# Sheet1.net
KiCad netlist of a schematic drawn in Altium Designer
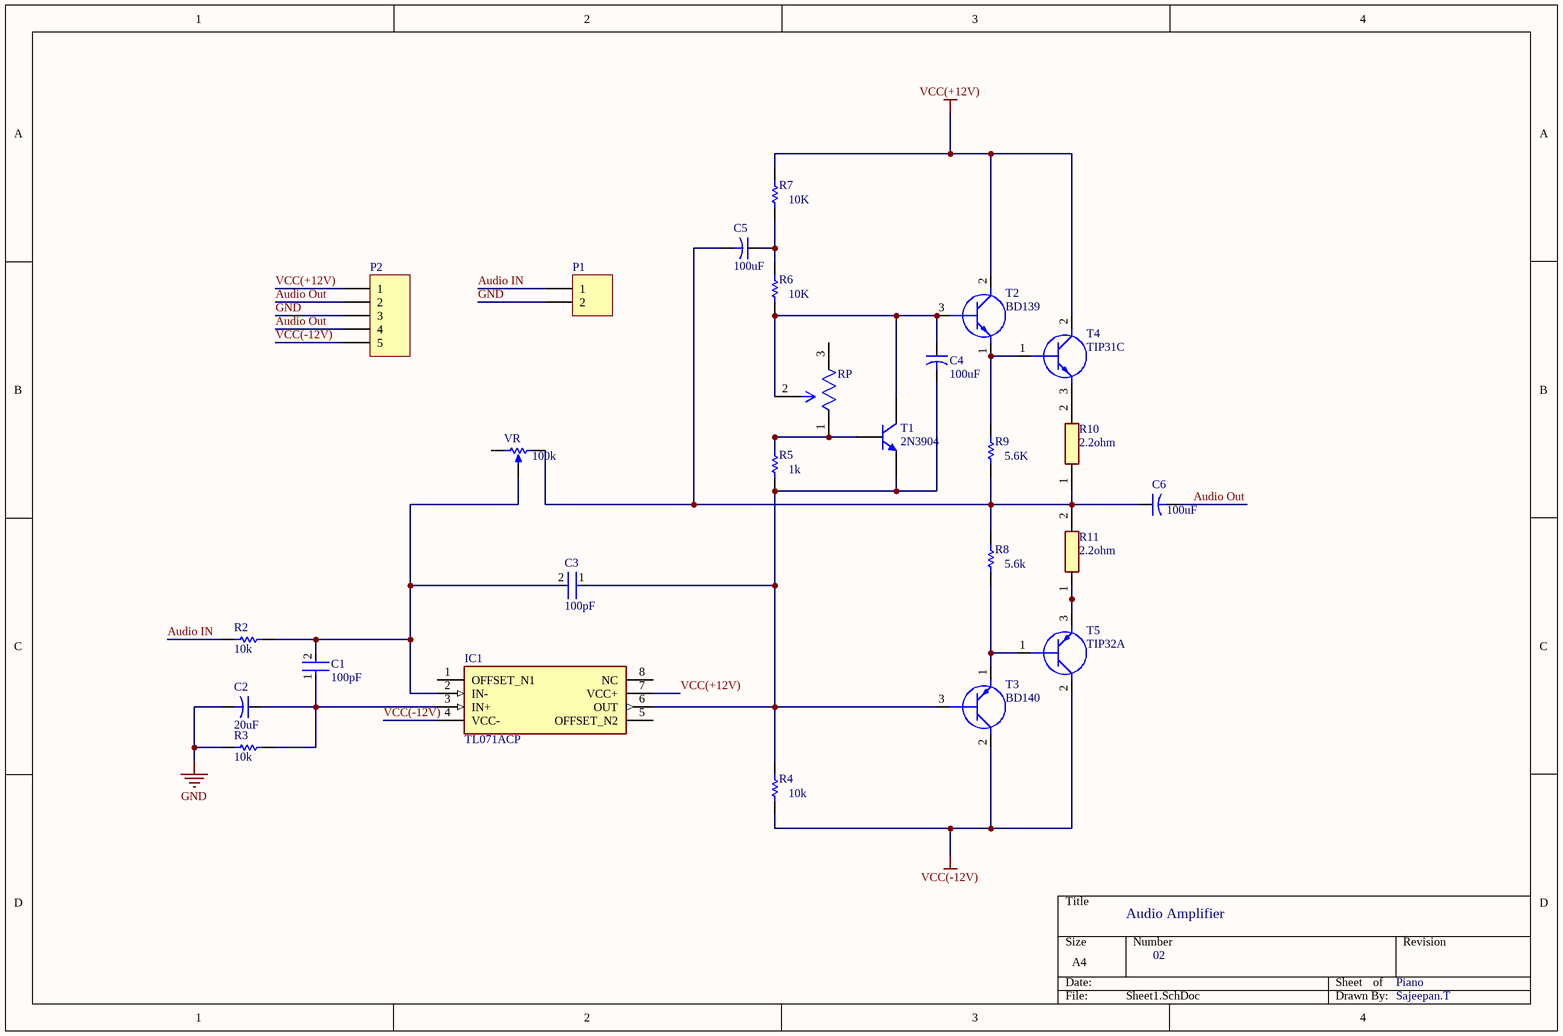
[diagram p0: Sheet1.SchDoc]

(export (version "E")
  (design (tool "Eeschema 10.0.6"))
  (components
    (comp (ref "C1")
      (value "100pF")
      (footprint "FP-RHS0DG-MFG")
      (description "CAP CER 100PF 100V CCG THRUHOLE")
      (fields (field (name "TOLERANCE") "5%") (field (name "MANUFACTURER") "Murata"))
      (libsource (lib "Altium Content Vault") (part "b4654b650e69147ec39a6b967a45e02"))
    )
    (comp (ref "C2")
      (value "20uF")
      (footprint "CAPR5-4X5")
      (description "Capacitor")
      (fields (field (name "Comment") "Cap2") (field (name "PUBLISHER") "Altium Limited"))
      (libsource (lib "Miscellaneous Devices") (part "Cap2"))
    )
    (comp (ref "C3")
      (value "100pF")
      (footprint "FP-RHS0DG-MFG")
      (description "CAP CER 100PF 100V CCG THRUHOLE")
      (fields (field (name "TOLERANCE") "5%") (field (name "MANUFACTURER") "Murata"))
      (libsource (lib "Altium Content Vault") (part "b4654b650e69147ec39a6b967a45e02"))
    )
    (comp (ref "C4")
      (value "100uF")
      (footprint "CAPR5-4X5")
      (description "Capacitor")
      (fields (field (name "Comment") "Cap2") (field (name "PUBLISHER") "Altium Limited"))
      (libsource (lib "Miscellaneous Devices") (part "Cap2"))
    )
    (comp (ref "C5")
      (value "100uF")
      (footprint "CAPR5-4X5")
      (description "Capacitor")
      (fields (field (name "Comment") "Cap2") (field (name "PUBLISHER") "Altium Limited"))
      (libsource (lib "Miscellaneous Devices") (part "Cap2"))
    )
    (comp (ref "C6")
      (value "100uF")
      (footprint "CAPR5-4X5")
      (description "Capacitor")
      (fields (field (name "Comment") "Cap2") (field (name "PUBLISHER") "Altium Limited"))
      (libsource (lib "Miscellaneous Devices") (part "Cap2"))
    )
    (comp (ref "IC1")
      (value "TL071ACP")
      (footprint "SamacSys:DIP794W53P254L959H508Q8N")
      (description "Integrated Circuit")
      (fields (field (name "MOUSER PART NUMBER") "595-TL071ACP"))
      (libsource (lib "*") (part "TL071ACP"))
    )
    (comp (ref "P1")
      (value "Header 2")
      (footprint "HDR1X2")
      (description "Header, 2-Pin")
      (fields (field (name "PUBLISHER") "Altium Limited"))
      (libsource (lib "Miscellaneous Connectors") (part "Header 2"))
    )
    (comp (ref "P2")
      (value "Header 5")
      (footprint "HDR1X5")
      (description "Header, 5-Pin")
      (fields (field (name "PUBLISHER") "Altium Limited"))
      (libsource (lib "Miscellaneous Connectors") (part "Header 5"))
    )
    (comp (ref "R2")
      (value "10k")
      (footprint "AXIAL-0.3")
      (description "Resistor")
      (fields (field (name "Comment") "Res1") (field (name "PUBLISHER") "Altium Limited"))
      (libsource (lib "Miscellaneous Devices") (part "Res1"))
    )
    (comp (ref "R3")
      (value "10k")
      (footprint "AXIAL-0.3")
      (description "Resistor")
      (fields (field (name "Comment") "Res1") (field (name "PUBLISHER") "Altium Limited"))
      (libsource (lib "Miscellaneous Devices") (part "Res1"))
    )
    (comp (ref "R4")
      (value "10k")
      (footprint "AXIAL-0.3")
      (description "Resistor")
      (fields (field (name "Comment") "Res1") (field (name "PUBLISHER") "Altium Limited"))
      (libsource (lib "Miscellaneous Devices") (part "Res1"))
    )
    (comp (ref "R5")
      (value "1k")
      (footprint "AXIAL-0.3")
      (description "Resistor")
      (fields (field (name "Comment") "Res1") (field (name "PUBLISHER") "Altium Limited"))
      (libsource (lib "Miscellaneous Devices") (part "Res1"))
    )
    (comp (ref "R6")
      (value "10K")
      (footprint "AXIAL-0.3")
      (description "Resistor")
      (fields (field (name "Comment") "Res1") (field (name "PUBLISHER") "Altium Limited"))
      (libsource (lib "Miscellaneous Devices") (part "Res1"))
    )
    (comp (ref "R7")
      (value "10K")
      (footprint "AXIAL-0.3")
      (description "Resistor")
      (fields (field (name "Comment") "Res1") (field (name "PUBLISHER") "Altium Limited"))
      (libsource (lib "Miscellaneous Devices") (part "Res1"))
    )
    (comp (ref "R8")
      (value "5.6k")
      (footprint "AXIAL-0.3")
      (description "Resistor")
      (fields (field (name "Comment") "Res1") (field (name "PUBLISHER") "Altium Limited"))
      (libsource (lib "Miscellaneous Devices") (part "Res1"))
    )
    (comp (ref "R9")
      (value "5.6K")
      (footprint "AXIAL-0.3")
      (description "Resistor")
      (fields (field (name "Comment") "Res1") (field (name "PUBLISHER") "Altium Limited"))
      (libsource (lib "Miscellaneous Devices") (part "Res1"))
    )
    (comp (ref "R10")
      (value "2.2ohm")
      (footprint "SamacSys:RESAD1130W50L370D190")
      (description "Resistor")
      (fields (field (name "MANUFACTURER_PART_NUMBER") "MFF04FF6800A5"))
      (libsource (lib "*") (part "MFF04FF6800A5"))
    )
    (comp (ref "R11")
      (value "2.2ohm")
      (footprint "SamacSys:RESAD1130W50L370D190")
      (description "Resistor")
      (fields (field (name "MANUFACTURER_PART_NUMBER") "MFF04FF6800A5"))
      (libsource (lib "*") (part "MFF04FF6800A5"))
    )
    (comp (ref "RP")
      (value "3386F-1-303LF")
      (footprint "FP-3386F-MFG")
      (description "TRIMMER 30K OHM 0.5W PC PIN TOP")
      (fields
        (field (name "TOLERANCE") "10%")
        (field (name "OCTOPART") "https://octopart.com/3386f-1-303lf-bourns-1032328")
      )
      (libsource (lib "Altium Content Vault") (part "f696fc322aeaec4039820165aa0401c"))
    )
    (comp (ref "T1")
      (value "2N3904")
      (footprint "TO-92A")
      (description "NPN General Purpose Amplifier")
      (fields (field (name "PUBLISHER") "Altium Limited"))
      (libsource (lib "Miscellaneous Devices") (part "2N3904"))
    )
    (comp (ref "T2")
      (value "BD139")
      (footprint "SamacSys:TO229P300X760X1364-3P")
      (description "Transistor BJT NPN")
      (fields (field (name "MOUSER PART NUMBER") "863-BD139"))
      (libsource (lib "*") (part "BD139"))
    )
    (comp (ref "T3")
      (value "BD140")
      (footprint "SamacSys:TO229P345X800X1460-3P")
      (description "Transistor BJT PNP")
      (fields
        (field (name "MANUFACTURER_PART_NUMBER") "BD14010STU")
        (field (name "MOUSER PART NUMBER") "512-BD14010STU")
      )
      (libsource (lib "*") (part "BD14010STU"))
    )
    (comp (ref "T4")
      (value "TIP31C")
      (footprint "SamacSys:TO254P470X1016X2019-3P")
      (description "Transistor BJT NPN")
      (libsource (lib "*") (part "TIP31C"))
    )
    (comp (ref "T5")
      (value "TIP32A")
      (footprint "SamacSys:TO254P470X1016X2019-3P")
      (description "Transistor BJT PNP")
      (fields (field (name "MOUSER PART NUMBER") "512-TIP32A"))
      (libsource (lib "*") (part "TIP32A"))
    )
    (comp (ref "VR")
      (value "100k")
      (footprint "BOUR-3852A-282-103AL-3_V")
      (description "Diameter Panel Control, 10 KOhm, +/- 10%, 2 W, -1 to 125 degC, 3-Pin THD, RoHS, Bulk")
      (fields (field (name "TOLERANCE") "±10%") (field (name "MANUFACTURER") "Bourns"))
      (libsource (lib "Altium Content Vault") (part "RES-POT-3"))
    )
  )
  (nets
    (net (code "1") (name "/Audio IN") (class "Default")
      (node (ref "P1") (pin "1") (pinfunction "1_1") (pintype "passive"))
      (node (ref "R2") (pin "2") (pinfunction "2_2") (pintype "passive"))
    )
    (net (code "2") (name "/Audio Out") (class "Default")
      (node (ref "C6") (pin "2") (pinfunction "2_2") (pintype "passive"))
      (node (ref "P2") (pin "2") (pinfunction "2_2") (pintype "passive"))
      (node (ref "P2") (pin "4") (pinfunction "4_4") (pintype "passive"))
    )
    (net (code "3") (name "GND") (class "Default")
      (node (ref "C2") (pin "2") (pinfunction "2_2") (pintype "passive"))
      (node (ref "P1") (pin "2") (pinfunction "2_2") (pintype "passive"))
      (node (ref "P2") (pin "3") (pinfunction "3_3") (pintype "passive"))
      (node (ref "R3") (pin "2") (pinfunction "2_2") (pintype "passive"))
    )
    (net (code "4") (name "Net-(C5-Pad1)") (class "Default")
      (node (ref "C5") (pin "1") (pinfunction "1_1") (pintype "passive"))
      (node (ref "R6") (pin "2") (pinfunction "2_2") (pintype "passive"))
      (node (ref "R7") (pin "1") (pinfunction "1_1") (pintype "passive"))
    )
    (net (code "5") (name "Net-(IC1-IN+)") (class "Default")
      (node (ref "C1") (pin "1") (pinfunction "1_1") (pintype "passive"))
      (node (ref "C2") (pin "1") (pinfunction "1_1") (pintype "passive"))
      (node (ref "IC1") (pin "3") (pinfunction "IN+_3") (pintype "input"))
      (node (ref "R3") (pin "1") (pinfunction "1_1") (pintype "passive"))
    )
    (net (code "6") (name "Net-(IC1-IN-)") (class "Default")
      (node (ref "C1") (pin "2") (pinfunction "2_2") (pintype "passive"))
      (node (ref "C3") (pin "2") (pinfunction "2_2") (pintype "passive"))
      (node (ref "IC1") (pin "2") (pinfunction "IN-_2") (pintype "input"))
      (node (ref "R2") (pin "1") (pinfunction "1_1") (pintype "passive"))
      (node (ref "VR") (pin "2") (pinfunction "S_2") (pintype "passive"))
    )
    (net (code "7") (name "Net-(IC1-OUT)") (class "Default")
      (node (ref "C3") (pin "1") (pinfunction "1_1") (pintype "passive"))
      (node (ref "C4") (pin "2") (pinfunction "2_2") (pintype "passive"))
      (node (ref "IC1") (pin "6") (pinfunction "OUT_6") (pintype "output"))
      (node (ref "R4") (pin "2") (pinfunction "2_2") (pintype "passive"))
      (node (ref "R5") (pin "1") (pinfunction "1_1") (pintype "passive"))
      (node (ref "T1") (pin "1") (pinfunction "E_1") (pintype "passive"))
      (node (ref "T3") (pin "3") (pinfunction "B_3") (pintype "passive"))
    )
    (net (code "8") (name "Net-(RP-CCW)") (class "Default")
      (node (ref "R5") (pin "2") (pinfunction "2_2") (pintype "passive"))
      (node (ref "RP") (pin "1") (pinfunction "CCW_1") (pintype "passive"))
      (node (ref "T1") (pin "2") (pinfunction "B_2") (pintype "passive"))
    )
    (net (code "9") (name "Net-(RP-WIPER)") (class "Default")
      (node (ref "C4") (pin "1") (pinfunction "1_1") (pintype "passive"))
      (node (ref "R6") (pin "1") (pinfunction "1_1") (pintype "passive"))
      (node (ref "RP") (pin "2") (pinfunction "WIPER_2") (pintype "passive"))
      (node (ref "T1") (pin "3") (pinfunction "C_3") (pintype "passive"))
      (node (ref "T2") (pin "3") (pinfunction "B_3") (pintype "passive"))
    )
    (net (code "10") (name "Net-(T2-E)") (class "Default")
      (node (ref "R9") (pin "2") (pinfunction "2_2") (pintype "passive"))
      (node (ref "T2") (pin "1") (pinfunction "E_1") (pintype "passive"))
      (node (ref "T4") (pin "1") (pinfunction "B_1") (pintype "passive"))
    )
    (net (code "11") (name "Net-(T3-E)") (class "Default")
      (node (ref "R8") (pin "1") (pinfunction "1_1") (pintype "passive"))
      (node (ref "T3") (pin "1") (pinfunction "E_1") (pintype "passive"))
      (node (ref "T5") (pin "1") (pinfunction "B_1") (pintype "passive"))
    )
    (net (code "12") (name "Net-(T4-E)") (class "Default")
      (node (ref "R10") (pin "2") (pinfunction "2_2") (pintype "passive"))
      (node (ref "T4") (pin "3") (pinfunction "E_3") (pintype "passive"))
    )
    (net (code "13") (name "Net-(T5-E)") (class "Default")
      (node (ref "R11") (pin "1") (pinfunction "1_1") (pintype "passive"))
      (node (ref "T5") (pin "3") (pinfunction "E_3") (pintype "passive"))
    )
    (net (code "14") (name "Net-(VR-CW)") (class "Default")
      (node (ref "C5") (pin "2") (pinfunction "2_2") (pintype "passive"))
      (node (ref "C6") (pin "1") (pinfunction "1_1") (pintype "passive"))
      (node (ref "R10") (pin "1") (pinfunction "1_1") (pintype "passive"))
      (node (ref "R11") (pin "2") (pinfunction "2_2") (pintype "passive"))
      (node (ref "R8") (pin "2") (pinfunction "2_2") (pintype "passive"))
      (node (ref "R9") (pin "1") (pinfunction "1_1") (pintype "passive"))
      (node (ref "VR") (pin "3") (pinfunction "CW_3") (pintype "passive"))
    )
    (net (code "15") (name "VCC(+12V)") (class "Default")
      (node (ref "IC1") (pin "7") (pinfunction "VCC+_7") (pintype "power_in"))
      (node (ref "P2") (pin "1") (pinfunction "1_1") (pintype "passive"))
      (node (ref "R7") (pin "2") (pinfunction "2_2") (pintype "passive"))
      (node (ref "T2") (pin "2") (pinfunction "C_2") (pintype "passive"))
      (node (ref "T4") (pin "2") (pinfunction "C_2") (pintype "passive"))
    )
    (net (code "16") (name "VCC(-12V)") (class "Default")
      (node (ref "IC1") (pin "4") (pinfunction "VCC-_4") (pintype "power_in"))
      (node (ref "P2") (pin "5") (pinfunction "5_5") (pintype "passive"))
      (node (ref "R4") (pin "1") (pinfunction "1_1") (pintype "passive"))
      (node (ref "T3") (pin "2") (pinfunction "C_2") (pintype "passive"))
      (node (ref "T5") (pin "2") (pinfunction "C_2") (pintype "passive"))
    )
    (net (code "17") (name "unconnected-(IC1-NC-Pad8)") (class "Default")
      (node (ref "IC1") (pin "8") (pinfunction "NC_8") (pintype "passive"))
    )
    (net (code "18") (name "unconnected-(IC1-OFFSET_N1-Pad1)") (class "Default")
      (node (ref "IC1") (pin "1") (pinfunction "OFFSET_N1_1") (pintype "passive"))
    )
    (net (code "19") (name "unconnected-(IC1-OFFSET_N2-Pad5)") (class "Default")
      (node (ref "IC1") (pin "5") (pinfunction "OFFSET_N2_5") (pintype "passive"))
    )
    (net (code "20") (name "unconnected-(RP-CW-Pad3)") (class "Default")
      (node (ref "RP") (pin "3") (pinfunction "CW_3") (pintype "passive"))
    )
    (net (code "21") (name "unconnected-(VR-CCW-Pad1)") (class "Default")
      (node (ref "VR") (pin "1") (pinfunction "CCW_1") (pintype "passive"))
    )
  )
)
